# PM_sensor_breakout_v1.net
KiCad netlist of a schematic drawn in EAGLE
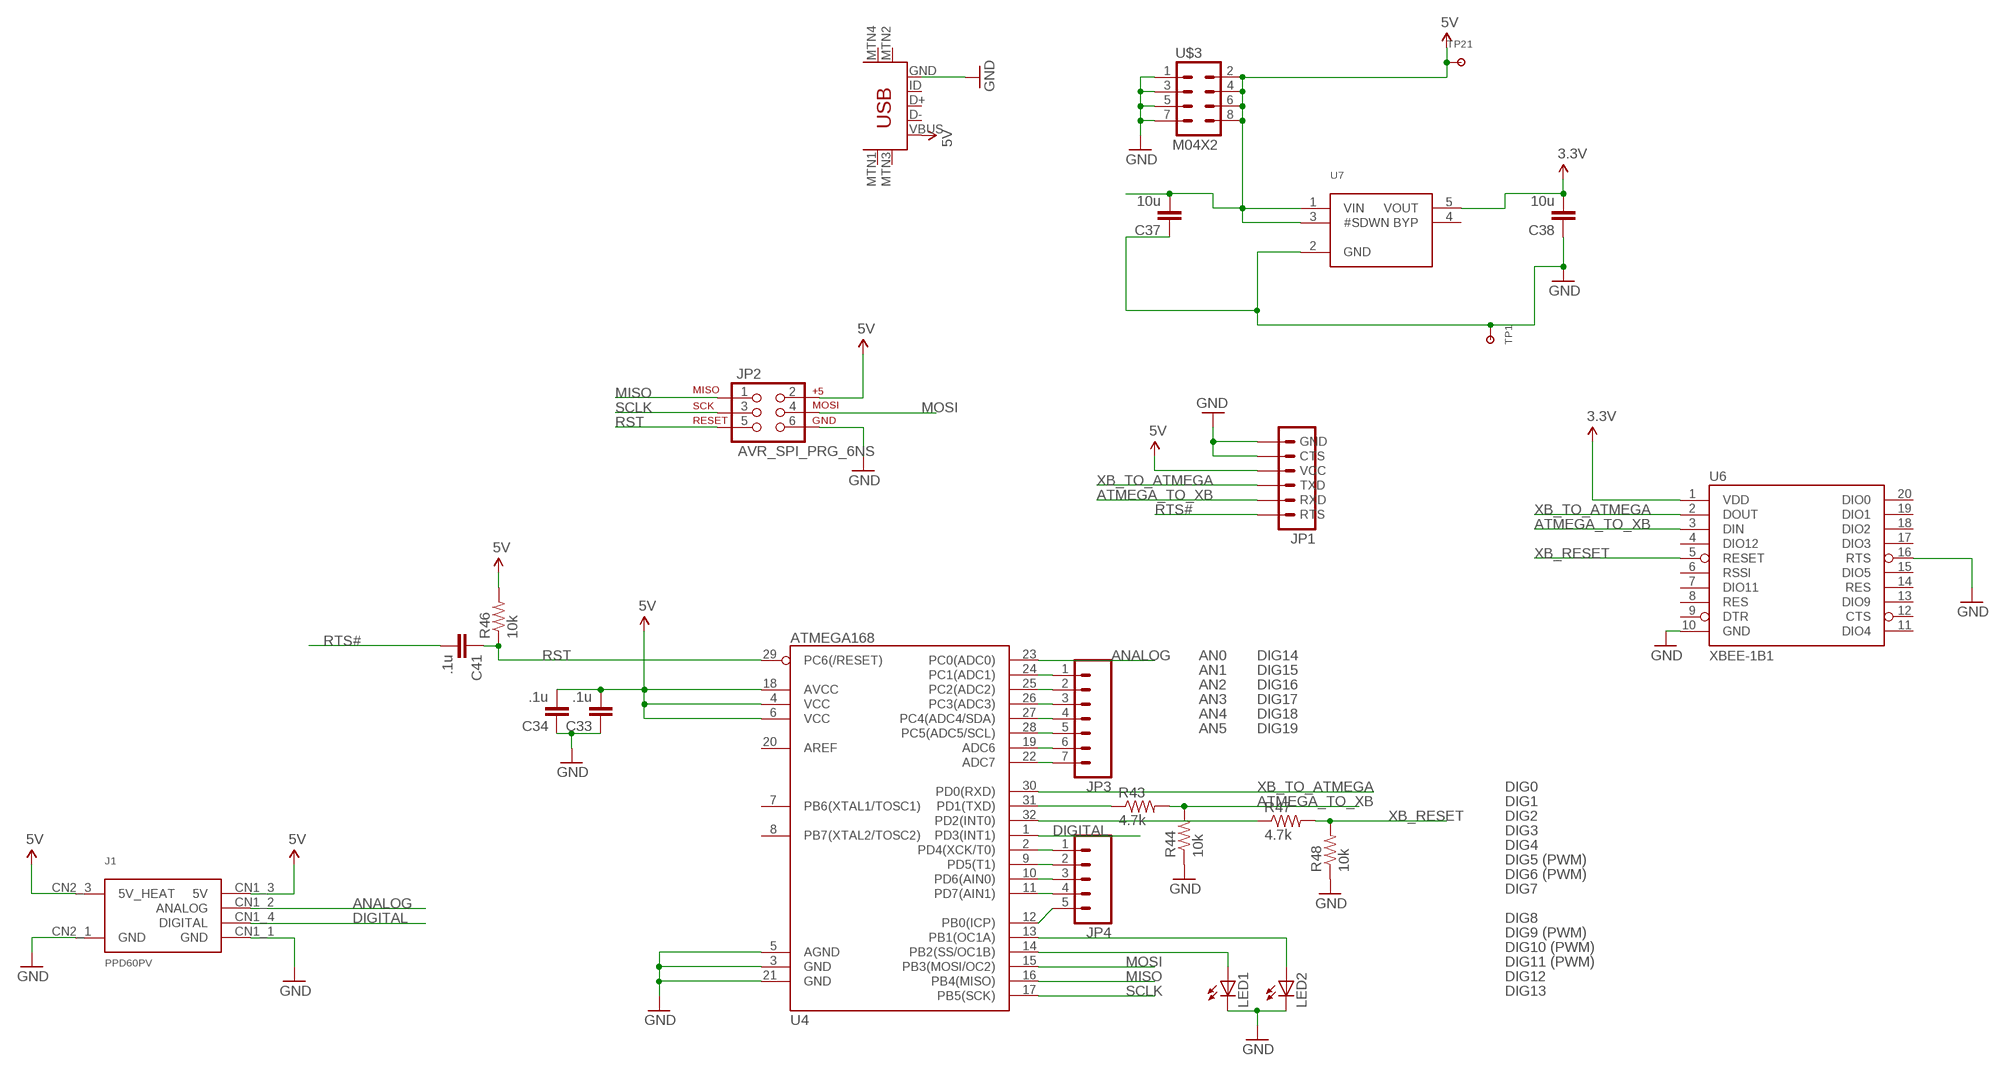
[diagram p0: schematic, sheet 1]

(export (version "E")
  (design (tool "Eeschema 10.0.6"))
  (components
    (comp (ref "C33")
      (value ".1u")
      (footprint "eagle-import:0603")
      (libsource (lib "eagle-import") (part "CAP0603"))
    )
    (comp (ref "C34")
      (value ".1u")
      (footprint "eagle-import:0603")
      (libsource (lib "eagle-import") (part "CAP0603"))
    )
    (comp (ref "C37")
      (value "10u")
      (footprint "eagle-import:0603")
      (libsource (lib "eagle-import") (part "CAP0603"))
    )
    (comp (ref "C38")
      (value "10u")
      (footprint "eagle-import:0603")
      (libsource (lib "eagle-import") (part "CAP0603"))
    )
    (comp (ref "C41")
      (value ".1u")
      (footprint "eagle-import:0603")
      (libsource (lib "eagle-import") (part "CAP0603"))
    )
    (comp (ref "J1")
      (value "PPD60PV")
      (footprint "eagle-import:PPD60PV")
      (libsource (lib "eagle-import") (part "PPD60PV"))
    )
    (comp (ref "JP1")
      (value "FTDI_CABLESIP")
      (footprint "eagle-import:1X06")
      (libsource (lib "eagle-import") (part "FTDI_CABLESIP"))
    )
    (comp (ref "JP2")
      (value "AVR_SPI_PRG_6NS")
      (footprint "eagle-import:2X3-NS")
      (libsource (lib "eagle-import") (part "AVR_SPI_PRG_6NS"))
    )
    (comp (ref "JP3")
      (value "M07")
      (footprint "eagle-import:1X07")
      (libsource (lib "eagle-import") (part "M07"))
    )
    (comp (ref "JP4")
      (value "M05PTH")
      (footprint "eagle-import:1X05")
      (libsource (lib "eagle-import") (part "M05PTH"))
    )
    (comp (ref "LED1")
      (value "LEDCHIPLED_0805")
      (footprint "eagle-import:CHIPLED_0805")
      (libsource (lib "eagle-import") (part "LEDCHIPLED_0805"))
    )
    (comp (ref "LED2")
      (value "LEDCHIPLED_0805")
      (footprint "eagle-import:CHIPLED_0805")
      (libsource (lib "eagle-import") (part "LEDCHIPLED_0805"))
    )
    (comp (ref "R43")
      (value "4.7k")
      (footprint "eagle-import:0603")
      (libsource (lib "eagle-import") (part "RESISTOR0603"))
    )
    (comp (ref "R44")
      (value "10k")
      (footprint "eagle-import:0603")
      (libsource (lib "eagle-import") (part "RESISTOR0603"))
    )
    (comp (ref "R46")
      (value "10k")
      (footprint "eagle-import:0603")
      (libsource (lib "eagle-import") (part "RESISTOR0603"))
    )
    (comp (ref "R47")
      (value "4.7k")
      (footprint "eagle-import:0603")
      (libsource (lib "eagle-import") (part "RESISTOR0603"))
    )
    (comp (ref "R48")
      (value "10k")
      (footprint "eagle-import:0603")
      (libsource (lib "eagle-import") (part "RESISTOR0603"))
    )
    (comp (ref "TP1")
      (value "TESTPOINT100MIL")
      (footprint "eagle-import:TESTPOINT-100MIL")
      (libsource (lib "eagle-import") (part "TESTPOINT100MIL"))
    )
    (comp (ref "TP21")
      (value "TESTPOINT100MIL")
      (footprint "eagle-import:TESTPOINT-100MIL")
      (libsource (lib "eagle-import") (part "TESTPOINT100MIL"))
    )
    (comp (ref "U$3")
      (value "M04X2")
      (footprint "eagle-import:2X4")
      (libsource (lib "eagle-import") (part "M04X2"))
    )
    (comp (ref "U$4")
      (value "USB-MINIB-5PIN")
      (footprint "eagle-import:USB-MINIB")
      (libsource (lib "eagle-import") (part "USB-MINIB-5PIN"))
    )
    (comp (ref "U4")
      (value "ATMEGA168")
      (footprint "eagle-import:TQFP32-08")
      (libsource (lib "eagle-import") (part "ATMEGA168"))
    )
    (comp (ref "U6")
      (value "XBEE-1B1")
      (footprint "eagle-import:XBEE-1")
      (libsource (lib "eagle-import") (part "XBEE-1B1"))
    )
    (comp (ref "U7")
      (value "LT1761-X")
      (footprint "eagle-import:TSOT23-5_LINEAR")
      (libsource (lib "eagle-import") (part "LT1761-X"))
    )
  )
  (nets
    (net (code "1") (name "/ANALOG") (class "Default")
      (node (ref "J1") (pin "CN1_2") (pinfunction "ANALOG_CN1_2") (pintype "bidirectional"))
      (node (ref "U4") (pin "23") (pinfunction "PC0(ADC0)_23") (pintype "bidirectional"))
    )
    (net (code "2") (name "/ATMEGA_TO_XB") (class "Default")
      (node (ref "JP1") (pin "5") (pinfunction "RXD_5") (pintype "passive"))
      (node (ref "R43") (pin "2") (pinfunction "2_2") (pintype "passive"))
      (node (ref "R44") (pin "2") (pinfunction "2_2") (pintype "passive"))
      (node (ref "U6") (pin "3") (pinfunction "DIN_3") (pintype "input"))
    )
    (net (code "3") (name "/DIGITAL") (class "Default")
      (node (ref "J1") (pin "CN1_4") (pinfunction "DIGITAL_CN1_4") (pintype "bidirectional"))
      (node (ref "U4") (pin "1") (pinfunction "PD3(INT1)_1") (pintype "bidirectional"))
    )
    (net (code "4") (name "/MISO") (class "Default")
      (node (ref "JP2") (pin "1") (pinfunction "1_1") (pintype "passive"))
      (node (ref "U4") (pin "16") (pinfunction "PB4(MISO)_16") (pintype "bidirectional"))
    )
    (net (code "5") (name "/MOSI") (class "Default")
      (node (ref "JP2") (pin "4") (pinfunction "4_4") (pintype "passive"))
      (node (ref "U4") (pin "15") (pinfunction "PB3(MOSI/OC2)_15") (pintype "bidirectional"))
    )
    (net (code "6") (name "/RST") (class "Default")
      (node (ref "C41") (pin "1") (pinfunction "1_1") (pintype "passive"))
      (node (ref "JP2") (pin "5") (pinfunction "5_5") (pintype "passive"))
      (node (ref "R46") (pin "1") (pinfunction "1_1") (pintype "passive"))
      (node (ref "U4") (pin "29") (pinfunction "PC6(/RESET)_29") (pintype "bidirectional"))
    )
    (net (code "7") (name "/RTS#") (class "Default")
      (node (ref "C41") (pin "2") (pinfunction "2_2") (pintype "passive"))
      (node (ref "JP1") (pin "6") (pinfunction "RTS_6") (pintype "passive"))
    )
    (net (code "8") (name "/SCLK") (class "Default")
      (node (ref "JP2") (pin "3") (pinfunction "3_3") (pintype "passive"))
      (node (ref "U4") (pin "17") (pinfunction "PB5(SCK)_17") (pintype "bidirectional"))
    )
    (net (code "9") (name "/XB_RESET") (class "Default")
      (node (ref "R47") (pin "2") (pinfunction "2_2") (pintype "passive"))
      (node (ref "R48") (pin "2") (pinfunction "2_2") (pintype "passive"))
      (node (ref "U6") (pin "5") (pinfunction "RESET_5") (pintype "input"))
    )
    (net (code "10") (name "/XB_TO_ATMEGA") (class "Default")
      (node (ref "JP1") (pin "4") (pinfunction "TXD_4") (pintype "passive"))
      (node (ref "U4") (pin "30") (pinfunction "PD0(RXD)_30") (pintype "bidirectional"))
      (node (ref "U6") (pin "2") (pinfunction "DOUT_2") (pintype "output"))
    )
    (net (code "11") (name "3.3V") (class "Default")
      (node (ref "C38") (pin "2") (pinfunction "2_2") (pintype "passive"))
      (node (ref "U6") (pin "1") (pinfunction "VDD_1") (pintype "power_in"))
      (node (ref "U7") (pin "5") (pinfunction "VOUT_5") (pintype "bidirectional"))
    )
    (net (code "12") (name "5V") (class "Default")
      (node (ref "C33") (pin "2") (pinfunction "2_2") (pintype "passive"))
      (node (ref "C34") (pin "2") (pinfunction "2_2") (pintype "passive"))
      (node (ref "C37") (pin "2") (pinfunction "2_2") (pintype "passive"))
      (node (ref "J1") (pin "CN1_3") (pinfunction "5V_CN1_3") (pintype "bidirectional"))
      (node (ref "J1") (pin "CN2_3") (pinfunction "5V_HEAT_CN2_3") (pintype "bidirectional"))
      (node (ref "JP1") (pin "3") (pinfunction "VCC_3") (pintype "passive"))
      (node (ref "JP2") (pin "2") (pinfunction "2_2") (pintype "passive"))
      (node (ref "R46") (pin "2") (pinfunction "2_2") (pintype "passive"))
      (node (ref "TP21") (pin "2") (pinfunction "P$1_2") (pintype "bidirectional"))
      (node (ref "U$3") (pin "2") (pinfunction "2_2") (pintype "passive"))
      (node (ref "U$3") (pin "4") (pinfunction "4_4") (pintype "passive"))
      (node (ref "U$3") (pin "6") (pinfunction "6_6") (pintype "passive"))
      (node (ref "U$3") (pin "8") (pinfunction "8_8") (pintype "passive"))
      (node (ref "U$4") (pin "VBUS") (pinfunction "VBUS_VBUS") (pintype "bidirectional"))
      (node (ref "U4") (pin "18") (pinfunction "AVCC_18") (pintype "bidirectional"))
      (node (ref "U4") (pin "4") (pinfunction "VCC_4") (pintype "bidirectional"))
      (node (ref "U4") (pin "6") (pinfunction "VCC_6") (pintype "bidirectional"))
      (node (ref "U7") (pin "1") (pinfunction "VIN_1") (pintype "bidirectional"))
      (node (ref "U7") (pin "3") (pinfunction "#SDWN_3") (pintype "bidirectional"))
    )
    (net (code "13") (name "GND") (class "Default")
      (node (ref "C33") (pin "1") (pinfunction "1_1") (pintype "passive"))
      (node (ref "C34") (pin "1") (pinfunction "1_1") (pintype "passive"))
      (node (ref "C37") (pin "1") (pinfunction "1_1") (pintype "passive"))
      (node (ref "C38") (pin "1") (pinfunction "1_1") (pintype "passive"))
      (node (ref "J1") (pin "CN1_1") (pinfunction "GND_CN1_1") (pintype "bidirectional"))
      (node (ref "J1") (pin "CN2_1") (pinfunction "GND_CN2_1") (pintype "bidirectional"))
      (node (ref "JP1") (pin "1") (pinfunction "GND_1") (pintype "passive"))
      (node (ref "JP1") (pin "2") (pinfunction "CTS_2") (pintype "passive"))
      (node (ref "JP2") (pin "6") (pinfunction "6_6") (pintype "passive"))
      (node (ref "LED1") (pin "C") (pinfunction "C_C") (pintype "passive"))
      (node (ref "LED2") (pin "C") (pinfunction "C_C") (pintype "passive"))
      (node (ref "R44") (pin "1") (pinfunction "1_1") (pintype "passive"))
      (node (ref "R48") (pin "1") (pinfunction "1_1") (pintype "passive"))
      (node (ref "TP1") (pin "2") (pinfunction "P$1_2") (pintype "bidirectional"))
      (node (ref "U$3") (pin "1") (pinfunction "1_1") (pintype "passive"))
      (node (ref "U$3") (pin "3") (pinfunction "3_3") (pintype "passive"))
      (node (ref "U$3") (pin "5") (pinfunction "5_5") (pintype "passive"))
      (node (ref "U$3") (pin "7") (pinfunction "7_7") (pintype "passive"))
      (node (ref "U$4") (pin "GND") (pinfunction "GND_GND") (pintype "bidirectional"))
      (node (ref "U4") (pin "21") (pinfunction "GND_21") (pintype "bidirectional"))
      (node (ref "U4") (pin "3") (pinfunction "GND_3") (pintype "bidirectional"))
      (node (ref "U4") (pin "5") (pinfunction "AGND_5") (pintype "bidirectional"))
      (node (ref "U6") (pin "10") (pinfunction "GND_10") (pintype "power_in"))
      (node (ref "U6") (pin "16") (pinfunction "RTS_16") (pintype "input"))
      (node (ref "U7") (pin "2") (pinfunction "GND_2") (pintype "bidirectional"))
    )
    (net (code "14") (name "Net-(U4-ADC6)") (class "Default")
      (node (ref "JP3") (pin "6") (pinfunction "6_6") (pintype "passive"))
      (node (ref "U4") (pin "19") (pinfunction "ADC6_19") (pintype "bidirectional"))
    )
    (net (code "15") (name "Net-(U4-ADC7)") (class "Default")
      (node (ref "JP3") (pin "7") (pinfunction "7_7") (pintype "passive"))
      (node (ref "U4") (pin "22") (pinfunction "ADC7_22") (pintype "bidirectional"))
    )
    (net (code "16") (name "Net-(U4-PB0(ICP))") (class "Default")
      (node (ref "JP4") (pin "5") (pinfunction "5_5") (pintype "passive"))
      (node (ref "U4") (pin "12") (pinfunction "PB0(ICP)_12") (pintype "bidirectional"))
    )
    (net (code "17") (name "Net-(U4-PB1(OC1A))") (class "Default")
      (node (ref "LED2") (pin "A") (pinfunction "A_A") (pintype "passive"))
      (node (ref "U4") (pin "13") (pinfunction "PB1(OC1A)_13") (pintype "bidirectional"))
    )
    (net (code "18") (name "Net-(U4-PB2(SS{slash}OC1B))") (class "Default")
      (node (ref "LED1") (pin "A") (pinfunction "A_A") (pintype "passive"))
      (node (ref "U4") (pin "14") (pinfunction "PB2(SS/OC1B)_14") (pintype "bidirectional"))
    )
    (net (code "19") (name "Net-(U4-PC1(ADC1))") (class "Default")
      (node (ref "JP3") (pin "1") (pinfunction "1_1") (pintype "passive"))
      (node (ref "U4") (pin "24") (pinfunction "PC1(ADC1)_24") (pintype "bidirectional"))
    )
    (net (code "20") (name "Net-(U4-PC2(ADC2))") (class "Default")
      (node (ref "JP3") (pin "2") (pinfunction "2_2") (pintype "passive"))
      (node (ref "U4") (pin "25") (pinfunction "PC2(ADC2)_25") (pintype "bidirectional"))
    )
    (net (code "21") (name "Net-(U4-PC3(ADC3))") (class "Default")
      (node (ref "JP3") (pin "3") (pinfunction "3_3") (pintype "passive"))
      (node (ref "U4") (pin "26") (pinfunction "PC3(ADC3)_26") (pintype "bidirectional"))
    )
    (net (code "22") (name "Net-(U4-PC4(ADC4{slash}SDA))") (class "Default")
      (node (ref "JP3") (pin "4") (pinfunction "4_4") (pintype "passive"))
      (node (ref "U4") (pin "27") (pinfunction "PC4(ADC4/SDA)_27") (pintype "bidirectional"))
    )
    (net (code "23") (name "Net-(U4-PC5(ADC5{slash}SCL))") (class "Default")
      (node (ref "JP3") (pin "5") (pinfunction "5_5") (pintype "passive"))
      (node (ref "U4") (pin "28") (pinfunction "PC5(ADC5/SCL)_28") (pintype "bidirectional"))
    )
    (net (code "24") (name "Net-(U4-PD1(TXD))") (class "Default")
      (node (ref "R43") (pin "1") (pinfunction "1_1") (pintype "passive"))
      (node (ref "U4") (pin "31") (pinfunction "PD1(TXD)_31") (pintype "bidirectional"))
    )
    (net (code "25") (name "Net-(U4-PD2(INT0))") (class "Default")
      (node (ref "R47") (pin "1") (pinfunction "1_1") (pintype "passive"))
      (node (ref "U4") (pin "32") (pinfunction "PD2(INT0)_32") (pintype "bidirectional"))
    )
    (net (code "26") (name "Net-(U4-PD4(XCK{slash}T0))") (class "Default")
      (node (ref "JP4") (pin "1") (pinfunction "1_1") (pintype "passive"))
      (node (ref "U4") (pin "2") (pinfunction "PD4(XCK/T0)_2") (pintype "bidirectional"))
    )
    (net (code "27") (name "Net-(U4-PD5(T1))") (class "Default")
      (node (ref "JP4") (pin "2") (pinfunction "2_2") (pintype "passive"))
      (node (ref "U4") (pin "9") (pinfunction "PD5(T1)_9") (pintype "bidirectional"))
    )
    (net (code "28") (name "Net-(U4-PD6(AIN0))") (class "Default")
      (node (ref "JP4") (pin "3") (pinfunction "3_3") (pintype "passive"))
      (node (ref "U4") (pin "10") (pinfunction "PD6(AIN0)_10") (pintype "bidirectional"))
    )
    (net (code "29") (name "Net-(U4-PD7(AIN1))") (class "Default")
      (node (ref "JP4") (pin "4") (pinfunction "4_4") (pintype "passive"))
      (node (ref "U4") (pin "11") (pinfunction "PD7(AIN1)_11") (pintype "bidirectional"))
    )
    (net (code "30") (name "unconnected-(U$4-MTN1-PadMTN3)") (class "Default")
      (node (ref "U$4") (pin "MTN3") (pinfunction "MTN1_MTN3") (pintype "bidirectional"))
    )
    (net (code "31") (name "unconnected-(U$4-MTN2-PadMTN1)") (class "Default")
      (node (ref "U$4") (pin "MTN1") (pinfunction "MTN2_MTN1") (pintype "bidirectional"))
    )
    (net (code "32") (name "unconnected-(U$4-MTN3-PadMTN2)") (class "Default")
      (node (ref "U$4") (pin "MTN2") (pinfunction "MTN3_MTN2") (pintype "bidirectional"))
    )
    (net (code "33") (name "unconnected-(U$4-PadD+)") (class "Default")
      (node (ref "U$4") (pin "D+") (pinfunction "D+_D+") (pintype "bidirectional"))
    )
    (net (code "34") (name "unconnected-(U$4-PadD-)") (class "Default")
      (node (ref "U$4") (pin "D-") (pinfunction "D-_D-") (pintype "bidirectional"))
    )
    (net (code "35") (name "unconnected-(U$4-PadID)") (class "Default")
      (node (ref "U$4") (pin "ID") (pinfunction "ID_ID") (pintype "bidirectional"))
    )
    (net (code "36") (name "unconnected-(U$4-PadMTN4)") (class "Default")
      (node (ref "U$4") (pin "MTN4") (pinfunction "MTN4_MTN4") (pintype "bidirectional"))
    )
    (net (code "37") (name "unconnected-(U4-AREF-Pad20)") (class "Default")
      (node (ref "U4") (pin "20") (pinfunction "AREF_20") (pintype "bidirectional"))
    )
    (net (code "38") (name "unconnected-(U4-PB6(XTAL1{slash}TOSC1)-Pad7)") (class "Default")
      (node (ref "U4") (pin "7") (pinfunction "PB6(XTAL1/TOSC1)_7") (pintype "bidirectional"))
    )
    (net (code "39") (name "unconnected-(U4-PB7(XTAL2{slash}TOSC2)-Pad8)") (class "Default")
      (node (ref "U4") (pin "8") (pinfunction "PB7(XTAL2/TOSC2)_8") (pintype "bidirectional"))
    )
    (net (code "40") (name "unconnected-(U6-CTS-Pad12)") (class "Default")
      (node (ref "U6") (pin "12") (pinfunction "CTS_12") (pintype "output"))
    )
    (net (code "41") (name "unconnected-(U6-DIO0-Pad20)") (class "Default")
      (node (ref "U6") (pin "20") (pinfunction "DIO0_20") (pintype "bidirectional"))
    )
    (net (code "42") (name "unconnected-(U6-DIO1-Pad19)") (class "Default")
      (node (ref "U6") (pin "19") (pinfunction "DIO1_19") (pintype "bidirectional"))
    )
    (net (code "43") (name "unconnected-(U6-DIO2-Pad18)") (class "Default")
      (node (ref "U6") (pin "18") (pinfunction "DIO2_18") (pintype "bidirectional"))
    )
    (net (code "44") (name "unconnected-(U6-DIO3-Pad17)") (class "Default")
      (node (ref "U6") (pin "17") (pinfunction "DIO3_17") (pintype "bidirectional"))
    )
    (net (code "45") (name "unconnected-(U6-DIO4-Pad11)") (class "Default")
      (node (ref "U6") (pin "11") (pinfunction "DIO4_11") (pintype "bidirectional"))
    )
    (net (code "46") (name "unconnected-(U6-DIO5-Pad15)") (class "Default")
      (node (ref "U6") (pin "15") (pinfunction "DIO5_15") (pintype "bidirectional"))
    )
    (net (code "47") (name "unconnected-(U6-DIO9-Pad13)") (class "Default")
      (node (ref "U6") (pin "13") (pinfunction "DIO9_13") (pintype "bidirectional"))
    )
    (net (code "48") (name "unconnected-(U6-DIO11-Pad7)") (class "Default")
      (node (ref "U6") (pin "7") (pinfunction "DIO11_7") (pintype "bidirectional"))
    )
    (net (code "49") (name "unconnected-(U6-DIO12-Pad4)") (class "Default")
      (node (ref "U6") (pin "4") (pinfunction "DIO12_4") (pintype "bidirectional"))
    )
    (net (code "50") (name "unconnected-(U6-DTR-Pad9)") (class "Default")
      (node (ref "U6") (pin "9") (pinfunction "DTR_9") (pintype "bidirectional"))
    )
    (net (code "51") (name "unconnected-(U6-RES-Pad8)") (class "Default")
      (node (ref "U6") (pin "8") (pinfunction "RES_8") (pintype "bidirectional"))
    )
    (net (code "52") (name "unconnected-(U6-RES-Pad14)") (class "Default")
      (node (ref "U6") (pin "14") (pinfunction "RES_14") (pintype "bidirectional"))
    )
    (net (code "53") (name "unconnected-(U6-RSSI-Pad6)") (class "Default")
      (node (ref "U6") (pin "6") (pinfunction "RSSI_6") (pintype "bidirectional"))
    )
    (net (code "54") (name "unconnected-(U7-BYP-Pad4)") (class "Default")
      (node (ref "U7") (pin "4") (pinfunction "BYP_4") (pintype "bidirectional"))
    )
  )
)
